# usb.net
KiCad netlist of a schematic drawn in Altium Designer
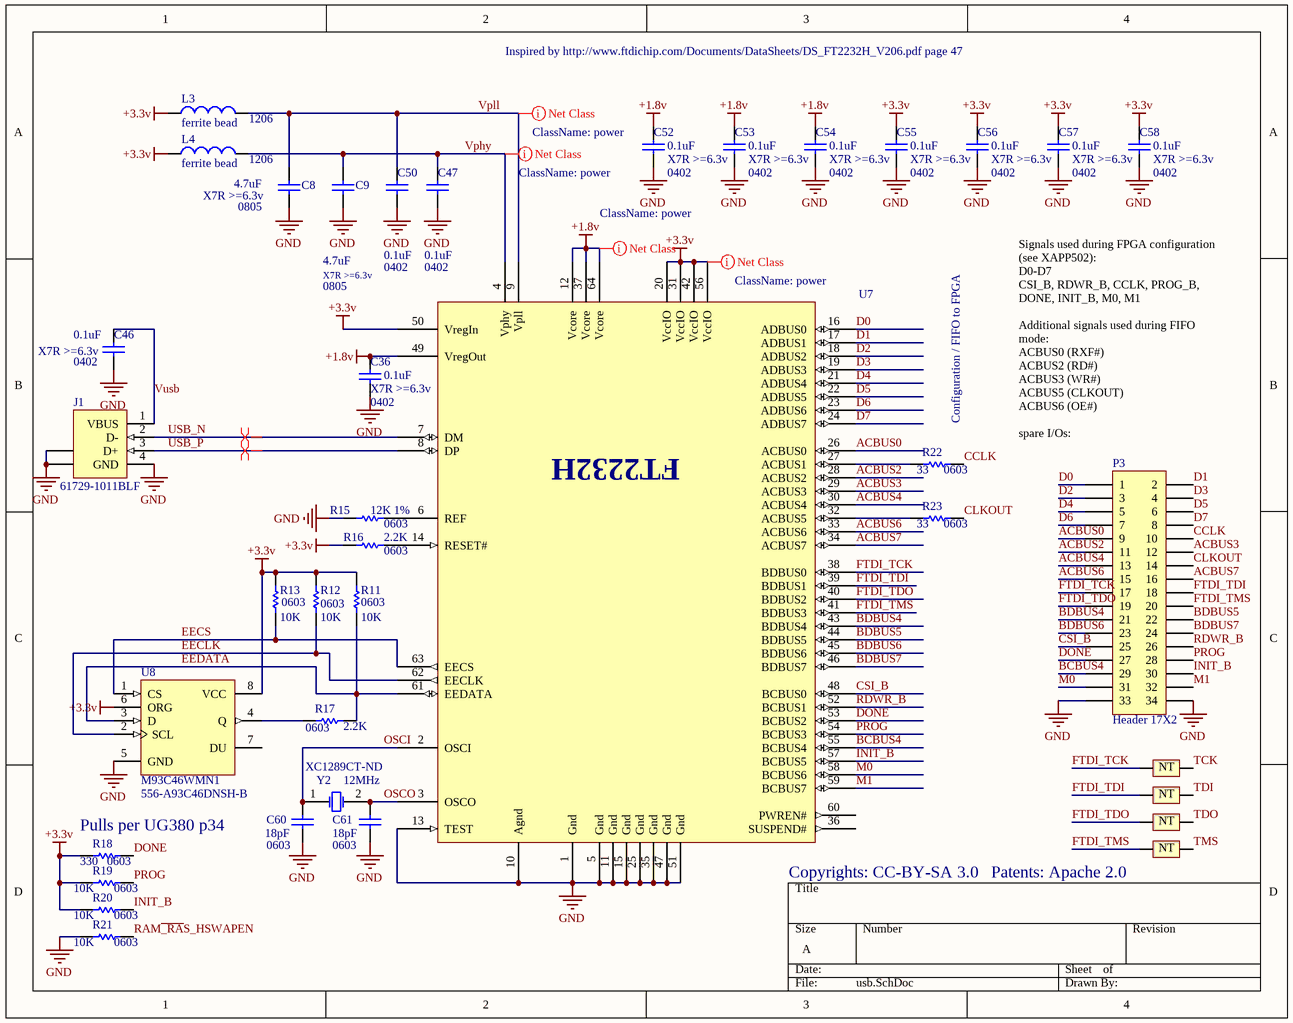
[diagram p0: usb.SchDoc]

(export (version "E")
  (design (tool "Eeschema 10.0.6"))
  (components
    (comp (ref "C8")
      (value "4.7uF")
      (footprint "CAPC2012N")
      (description "CAP CER 4.7UF 10V Y5V 0805")
      (fields
        (field (name "PACKAGEREFERENCE") "0805")
        (field (name "TOLERANCE") "-20%, +80%")
        (field (name "RATING") "X7R >=6.3v")
      )
      (libsource (lib "Miscellaneous Devices") (part "Cap"))
    )
    (comp (ref "C9")
      (value "4.7uF")
      (footprint "CAPC2012N")
      (description "CAP CER 4.7UF 10V Y5V 0805")
      (fields
        (field (name "PACKAGEREFERENCE") "0805")
        (field (name "TOLERANCE") "-20%, +80%")
        (field (name "RATING") "X7R >=6.3v")
      )
      (libsource (lib "Miscellaneous Devices") (part "Cap"))
    )
    (comp (ref "C36")
      (value "0.1uF")
      (footprint "CAPC1005N")
      (description "CAP CER 0.1UF 25V 10% X5R 0603")
      (fields
        (field (name "PACKAGEREFERENCE") "0402")
        (field (name "TOLERANCE") "±10%")
        (field (name "RATING") "X7R >=6.3v")
      )
      (libsource (lib "Miscellaneous Devices") (part "Cap Semi"))
    )
    (comp (ref "C46")
      (value "0.1uF")
      (footprint "CAPC1005N")
      (description "CAP CER 0.1UF 25V 10% X5R 0603")
      (fields
        (field (name "PACKAGEREFERENCE") "0402")
        (field (name "TOLERANCE") "±10%")
        (field (name "RATING") "X7R >=6.3v")
      )
      (libsource (lib "Miscellaneous Devices") (part "Cap Semi"))
    )
    (comp (ref "C47")
      (value "0.1uF")
      (footprint "CAPC1005N")
      (description "CAP CER 0.1UF 25V 10% X5R 0603")
      (fields (field (name "PACKAGEREFERENCE") "0402") (field (name "TOLERANCE") "±10%"))
      (libsource (lib "Miscellaneous Devices") (part "Cap Semi"))
    )
    (comp (ref "C50")
      (value "0.1uF")
      (footprint "CAPC1005N")
      (description "CAP CER 0.1UF 25V 10% X5R 0603")
      (fields (field (name "PACKAGEREFERENCE") "0402") (field (name "TOLERANCE") "±10%"))
      (libsource (lib "Miscellaneous Devices") (part "Cap Semi"))
    )
    (comp (ref "C52")
      (value "0.1uF")
      (footprint "CAPC1005N")
      (description "CAP CER 0.1UF 25V 10% X5R 0603")
      (fields
        (field (name "PACKAGEREFERENCE") "0402")
        (field (name "TOLERANCE") "±10%")
        (field (name "RATING") "X7R >=6.3v")
      )
      (libsource (lib "Miscellaneous Devices") (part "Cap Semi"))
    )
    (comp (ref "C53")
      (value "0.1uF")
      (footprint "CAPC1005N")
      (description "CAP CER 0.1UF 25V 10% X5R 0603")
      (fields
        (field (name "PACKAGEREFERENCE") "0402")
        (field (name "TOLERANCE") "±10%")
        (field (name "RATING") "X7R >=6.3v")
      )
      (libsource (lib "Miscellaneous Devices") (part "Cap Semi"))
    )
    (comp (ref "C54")
      (value "0.1uF")
      (footprint "CAPC1005N")
      (description "CAP CER 0.1UF 25V 10% X5R 0603")
      (fields
        (field (name "PACKAGEREFERENCE") "0402")
        (field (name "TOLERANCE") "±10%")
        (field (name "RATING") "X7R >=6.3v")
      )
      (libsource (lib "Miscellaneous Devices") (part "Cap Semi"))
    )
    (comp (ref "C55")
      (value "0.1uF")
      (footprint "CAPC1005N")
      (description "CAP CER 0.1UF 25V 10% X5R 0603")
      (fields
        (field (name "PACKAGEREFERENCE") "0402")
        (field (name "TOLERANCE") "±10%")
        (field (name "RATING") "X7R >=6.3v")
      )
      (libsource (lib "Miscellaneous Devices") (part "Cap Semi"))
    )
    (comp (ref "C56")
      (value "0.1uF")
      (footprint "CAPC1005N")
      (description "CAP CER 0.1UF 25V 10% X5R 0603")
      (fields
        (field (name "PACKAGEREFERENCE") "0402")
        (field (name "TOLERANCE") "±10%")
        (field (name "RATING") "X7R >=6.3v")
      )
      (libsource (lib "Miscellaneous Devices") (part "Cap Semi"))
    )
    (comp (ref "C57")
      (value "0.1uF")
      (footprint "CAPC1005N")
      (description "CAP CER 0.1UF 25V 10% X5R 0603")
      (fields
        (field (name "PACKAGEREFERENCE") "0402")
        (field (name "TOLERANCE") "±10%")
        (field (name "RATING") "X7R >=6.3v")
      )
      (libsource (lib "Miscellaneous Devices") (part "Cap Semi"))
    )
    (comp (ref "C58")
      (value "0.1uF")
      (footprint "CAPC1005N")
      (description "CAP CER 0.1UF 25V 10% X5R 0603")
      (fields
        (field (name "PACKAGEREFERENCE") "0402")
        (field (name "TOLERANCE") "±10%")
        (field (name "RATING") "X7R >=6.3v")
      )
      (libsource (lib "Miscellaneous Devices") (part "Cap Semi"))
    )
    (comp (ref "C60")
      (value "18pF")
      (footprint "Chip_Capacitor_N:CAPC1608N")
      (description "Capacitor (Semiconductor SIM Model)")
      (fields (field (name "PACKAGEREFERENCE") "0603") (field (name "Comment") "Cap Semi"))
      (libsource (lib "Miscellaneous Devices") (part "Cap Semi"))
    )
    (comp (ref "C61")
      (value "18pF")
      (footprint "Chip_Capacitor_N:CAPC1608N")
      (description "Capacitor (Semiconductor SIM Model)")
      (fields (field (name "PACKAGEREFERENCE") "0603") (field (name "Comment") "Cap Semi"))
      (libsource (lib "Miscellaneous Devices") (part "Cap Semi"))
    )
    (comp (ref "J1")
      (value "61729-1011BLF")
      (footprint "1-1470156")
      (description "USB 1.1, Right Angle, Thru-Hole, B Type, Receptacle, 4 Position, White")
      (fields (field (name "Comment") "1-1470156-1"))
      (libsource (lib "AMP Serial Bus USB") (part "1-1470156-1"))
    )
    (comp (ref "L3")
      (value "ferrite bead")
      (footprint "INDC3216AN")
      (description "Inductor")
      (fields (field (name "PACKAGEREFERENCE") "1206"))
      (libsource (lib "Miscellaneous Devices") (part "Inductor"))
    )
    (comp (ref "L4")
      (value "ferrite bead")
      (footprint "INDC3216AN")
      (description "Inductor")
      (fields (field (name "PACKAGEREFERENCE") "1206"))
      (libsource (lib "Miscellaneous Devices") (part "Inductor"))
    )
    (comp (ref "NT2")
      (value "Net Tie2")
      (footprint "NetTie 0603")
      (description "0603 Net Tie to connect 2 different nets")
      (libsource (lib "OpenVizsla symbols") (part "Net Tie2"))
    )
    (comp (ref "NT3")
      (value "Net Tie2")
      (footprint "NetTie 0603")
      (description "0603 Net Tie to connect 2 different nets")
      (libsource (lib "OpenVizsla symbols") (part "Net Tie2"))
    )
    (comp (ref "NT4")
      (value "Net Tie2")
      (footprint "NetTie 0603")
      (description "0603 Net Tie to connect 2 different nets")
      (libsource (lib "OpenVizsla symbols") (part "Net Tie2"))
    )
    (comp (ref "NT5")
      (value "Net Tie2")
      (footprint "NetTie 0603")
      (description "0603 Net Tie to connect 2 different nets")
      (libsource (lib "OpenVizsla symbols") (part "Net Tie2"))
    )
    (comp (ref "P3")
      (value "Header 17X2")
      (footprint "HDR2X17")
      (description "Header, 17-Pin, Dual row")
      (libsource (lib "Miscellaneous Connectors") (part "Header 17X2"))
    )
    (comp (ref "R11")
      (value "10K")
      (footprint "RESC1608N")
      (description "Semiconductor Resistor")
      (fields (field (name "PACKAGEREFERENCE") "0603") (field (name "Comment") "Res Semi"))
      (libsource (lib "Miscellaneous Devices") (part "Res Semi"))
    )
    (comp (ref "R12")
      (value "10K")
      (footprint "RESC1608N")
      (description "Semiconductor Resistor")
      (fields (field (name "PACKAGEREFERENCE") "0603") (field (name "Comment") "Res Semi"))
      (libsource (lib "Miscellaneous Devices") (part "Res Semi"))
    )
    (comp (ref "R13")
      (value "10K")
      (footprint "RESC1608N")
      (description "Semiconductor Resistor")
      (fields (field (name "PACKAGEREFERENCE") "0603") (field (name "Comment") "Res Semi"))
      (libsource (lib "Miscellaneous Devices") (part "Res Semi"))
    )
    (comp (ref "R15")
      (value "12K 1%")
      (footprint "RESC1608N")
      (description "Semiconductor Resistor")
      (fields (field (name "PACKAGEREFERENCE") "0603") (field (name "Comment") "Res Semi"))
      (libsource (lib "Miscellaneous Devices") (part "Res Semi"))
    )
    (comp (ref "R16")
      (value "2.2K")
      (footprint "RESC1608N")
      (description "Semiconductor Resistor")
      (fields (field (name "PACKAGEREFERENCE") "0603") (field (name "Comment") "Res Semi"))
      (libsource (lib "Miscellaneous Devices") (part "Res Semi"))
    )
    (comp (ref "R17")
      (value "2.2K")
      (footprint "RESC1608N")
      (description "Semiconductor Resistor")
      (fields (field (name "PACKAGEREFERENCE") "0603") (field (name "Comment") "Res Semi"))
      (libsource (lib "Miscellaneous Devices") (part "Res Semi"))
    )
    (comp (ref "R18")
      (value "330")
      (footprint "RESC1608N")
      (description "Semiconductor Resistor")
      (fields (field (name "PACKAGEREFERENCE") "0603") (field (name "Comment") "Res Semi"))
      (libsource (lib "Miscellaneous Devices") (part "Res Semi"))
    )
    (comp (ref "R19")
      (value "10K")
      (footprint "RESC1608N")
      (description "Semiconductor Resistor")
      (fields (field (name "PACKAGEREFERENCE") "0603") (field (name "Comment") "Res Semi"))
      (libsource (lib "Miscellaneous Devices") (part "Res Semi"))
    )
    (comp (ref "R20")
      (value "10K")
      (footprint "RESC1608N")
      (description "Semiconductor Resistor")
      (fields (field (name "PACKAGEREFERENCE") "0603") (field (name "Comment") "Res Semi"))
      (libsource (lib "Miscellaneous Devices") (part "Res Semi"))
    )
    (comp (ref "R21")
      (value "10K")
      (footprint "RESC1608N")
      (description "Semiconductor Resistor")
      (fields (field (name "PACKAGEREFERENCE") "0603") (field (name "Comment") "Res Semi"))
      (libsource (lib "Miscellaneous Devices") (part "Res Semi"))
    )
    (comp (ref "R22")
      (value "33")
      (footprint "RESC1608N")
      (description "Semiconductor Resistor")
      (fields (field (name "PACKAGEREFERENCE") "0603") (field (name "Comment") "Res Semi"))
      (libsource (lib "Miscellaneous Devices") (part "Res Semi"))
    )
    (comp (ref "R23")
      (value "33")
      (footprint "RESC1608N")
      (description "Semiconductor Resistor")
      (fields (field (name "PACKAGEREFERENCE") "0603") (field (name "Comment") "Res Semi"))
      (libsource (lib "Miscellaneous Devices") (part "Res Semi"))
    )
    (comp (ref "U7")
      (value "Component_1")
      (footprint "SQFP50P1200X1200X180-64N")
      (description "FT2232H")
      (libsource (lib "ftdi") (part "Component_1"))
    )
    (comp (ref "U8")
      (value "M93C46WMN1")
      (footprint "SOP8_N")
      (description "1Kb (x8/x16) Serial Microwire Bus EEPROM")
      (fields (field (name "SUPPLIER PART NUMBER 1") "556-A93C46DNSH-B"))
      (libsource (lib "ST Memory EEPROM Serial") (part "M93C46WMN1"))
    )
    (comp (ref "Y2")
      (value "12MHz")
      (footprint "HC49/4H_SMX")
      (description "Crystal Oscillator")
      (fields (field (name "SUPPLIER PART NUMBER 1") "XC1289CT-ND"))
      (libsource (lib "Miscellaneous Devices") (part "XTAL"))
    )
  )
  (nets
    (net (code "1") (name "+1.8v") (class "Default")
      (node (ref "C36") (pin "2") (pinfunction "2_2") (pintype "passive"))
      (node (ref "C52") (pin "2") (pinfunction "2_2") (pintype "passive"))
      (node (ref "C53") (pin "2") (pinfunction "2_2") (pintype "passive"))
      (node (ref "C54") (pin "2") (pinfunction "2_2") (pintype "passive"))
      (node (ref "U7") (pin "12") (pinfunction "Vcore_12") (pintype "power_in"))
      (node (ref "U7") (pin "37") (pinfunction "Vcore_37") (pintype "power_in"))
      (node (ref "U7") (pin "49") (pinfunction "VregOut_49") (pintype "power_in"))
      (node (ref "U7") (pin "64") (pinfunction "Vcore_64") (pintype "power_in"))
    )
    (net (code "2") (name "+3.3v") (class "Default")
      (node (ref "C55") (pin "2") (pinfunction "2_2") (pintype "passive"))
      (node (ref "C56") (pin "2") (pinfunction "2_2") (pintype "passive"))
      (node (ref "C57") (pin "2") (pinfunction "2_2") (pintype "passive"))
      (node (ref "C58") (pin "2") (pinfunction "2_2") (pintype "passive"))
      (node (ref "L3") (pin "1") (pinfunction "1_1") (pintype "passive"))
      (node (ref "L4") (pin "1") (pinfunction "1_1") (pintype "passive"))
      (node (ref "R11") (pin "2") (pinfunction "2_2") (pintype "passive"))
      (node (ref "R12") (pin "2") (pinfunction "2_2") (pintype "passive"))
      (node (ref "R13") (pin "2") (pinfunction "2_2") (pintype "passive"))
      (node (ref "R16") (pin "1") (pinfunction "1_1") (pintype "passive"))
      (node (ref "R18") (pin "2") (pinfunction "2_2") (pintype "passive"))
      (node (ref "R19") (pin "1") (pinfunction "1_1") (pintype "passive"))
      (node (ref "R20") (pin "1") (pinfunction "1_1") (pintype "passive"))
      (node (ref "U7") (pin "20") (pinfunction "VccIO_20") (pintype "power_in"))
      (node (ref "U7") (pin "31") (pinfunction "VccIO_31") (pintype "power_in"))
      (node (ref "U7") (pin "42") (pinfunction "VccIO_42") (pintype "power_in"))
      (node (ref "U7") (pin "50") (pinfunction "VregIn_50") (pintype "power_in"))
      (node (ref "U7") (pin "56") (pinfunction "VccIO_56") (pintype "power_in"))
      (node (ref "U8") (pin "6") (pinfunction "ORG_6") (pintype "passive"))
      (node (ref "U8") (pin "8") (pinfunction "VCC_8") (pintype "power_in"))
    )
    (net (code "3") (name "/ACBUS0") (class "Default")
      (node (ref "P3") (pin "9") (pinfunction "9_9") (pintype "passive"))
      (node (ref "U7") (pin "26") (pinfunction "ACBUS0_26") (pintype "bidirectional"))
    )
    (net (code "4") (name "/ACBUS2") (class "Default")
      (node (ref "P3") (pin "11") (pinfunction "11_11") (pintype "passive"))
      (node (ref "U7") (pin "28") (pinfunction "ACBUS2_28") (pintype "bidirectional"))
    )
    (net (code "5") (name "/ACBUS3") (class "Default")
      (node (ref "P3") (pin "12") (pinfunction "12_12") (pintype "passive"))
      (node (ref "U7") (pin "29") (pinfunction "ACBUS3_29") (pintype "bidirectional"))
    )
    (net (code "6") (name "/ACBUS4") (class "Default")
      (node (ref "P3") (pin "13") (pinfunction "13_13") (pintype "passive"))
      (node (ref "U7") (pin "30") (pinfunction "ACBUS4_30") (pintype "bidirectional"))
    )
    (net (code "7") (name "/ACBUS6") (class "Default")
      (node (ref "P3") (pin "15") (pinfunction "15_15") (pintype "passive"))
      (node (ref "U7") (pin "33") (pinfunction "ACBUS6_33") (pintype "bidirectional"))
    )
    (net (code "8") (name "/ACBUS7") (class "Default")
      (node (ref "P3") (pin "16") (pinfunction "16_16") (pintype "passive"))
      (node (ref "U7") (pin "34") (pinfunction "ACBUS7_34") (pintype "bidirectional"))
    )
    (net (code "9") (name "/BCBUS4") (class "Default")
      (node (ref "P3") (pin "29") (pinfunction "29_29") (pintype "passive"))
      (node (ref "U7") (pin "55") (pinfunction "BCBUS4_55") (pintype "bidirectional"))
    )
    (net (code "10") (name "/BDBUS4") (class "Default")
      (node (ref "P3") (pin "21") (pinfunction "21_21") (pintype "passive"))
      (node (ref "U7") (pin "43") (pinfunction "BDBUS4_43") (pintype "bidirectional"))
    )
    (net (code "11") (name "/BDBUS5") (class "Default")
      (node (ref "P3") (pin "22") (pinfunction "22_22") (pintype "passive"))
      (node (ref "U7") (pin "44") (pinfunction "BDBUS5_44") (pintype "bidirectional"))
    )
    (net (code "12") (name "/BDBUS6") (class "Default")
      (node (ref "P3") (pin "23") (pinfunction "23_23") (pintype "passive"))
      (node (ref "U7") (pin "45") (pinfunction "BDBUS6_45") (pintype "bidirectional"))
    )
    (net (code "13") (name "/BDBUS7") (class "Default")
      (node (ref "P3") (pin "24") (pinfunction "24_24") (pintype "passive"))
      (node (ref "U7") (pin "46") (pinfunction "BDBUS7_46") (pintype "bidirectional"))
    )
    (net (code "14") (name "/CCLK") (class "Default")
      (node (ref "P3") (pin "10") (pinfunction "10_10") (pintype "passive"))
      (node (ref "R22") (pin "2") (pinfunction "2_2") (pintype "passive"))
    )
    (net (code "15") (name "/CLKOUT") (class "Default")
      (node (ref "P3") (pin "14") (pinfunction "14_14") (pintype "passive"))
      (node (ref "R23") (pin "2") (pinfunction "2_2") (pintype "passive"))
    )
    (net (code "16") (name "/CSI_B") (class "Default")
      (node (ref "P3") (pin "25") (pinfunction "25_25") (pintype "passive"))
      (node (ref "U7") (pin "48") (pinfunction "BCBUS0_48") (pintype "bidirectional"))
    )
    (net (code "17") (name "/D0") (class "Default")
      (node (ref "P3") (pin "1") (pinfunction "1_1") (pintype "passive"))
      (node (ref "U7") (pin "16") (pinfunction "ADBUS0_16") (pintype "bidirectional"))
    )
    (net (code "18") (name "/D1") (class "Default")
      (node (ref "P3") (pin "2") (pinfunction "2_2") (pintype "passive"))
      (node (ref "U7") (pin "17") (pinfunction "ADBUS1_17") (pintype "bidirectional"))
    )
    (net (code "19") (name "/D2") (class "Default")
      (node (ref "P3") (pin "3") (pinfunction "3_3") (pintype "passive"))
      (node (ref "U7") (pin "18") (pinfunction "ADBUS2_18") (pintype "bidirectional"))
    )
    (net (code "20") (name "/D3") (class "Default")
      (node (ref "P3") (pin "4") (pinfunction "4_4") (pintype "passive"))
      (node (ref "U7") (pin "19") (pinfunction "ADBUS3_19") (pintype "bidirectional"))
    )
    (net (code "21") (name "/D4") (class "Default")
      (node (ref "P3") (pin "5") (pinfunction "5_5") (pintype "passive"))
      (node (ref "U7") (pin "21") (pinfunction "ADBUS4_21") (pintype "bidirectional"))
    )
    (net (code "22") (name "/D5") (class "Default")
      (node (ref "P3") (pin "6") (pinfunction "6_6") (pintype "passive"))
      (node (ref "U7") (pin "22") (pinfunction "ADBUS5_22") (pintype "bidirectional"))
    )
    (net (code "23") (name "/D6") (class "Default")
      (node (ref "P3") (pin "7") (pinfunction "7_7") (pintype "passive"))
      (node (ref "U7") (pin "23") (pinfunction "ADBUS6_23") (pintype "bidirectional"))
    )
    (net (code "24") (name "/D7") (class "Default")
      (node (ref "P3") (pin "8") (pinfunction "8_8") (pintype "passive"))
      (node (ref "U7") (pin "24") (pinfunction "ADBUS7_24") (pintype "bidirectional"))
    )
    (net (code "25") (name "/DONE") (class "Default")
      (node (ref "P3") (pin "27") (pinfunction "27_27") (pintype "passive"))
      (node (ref "R18") (pin "1") (pinfunction "1_1") (pintype "passive"))
      (node (ref "U7") (pin "53") (pinfunction "BCBUS2_53") (pintype "bidirectional"))
    )
    (net (code "26") (name "/EECLK") (class "Default")
      (node (ref "R12") (pin "1") (pinfunction "1_1") (pintype "passive"))
      (node (ref "U7") (pin "62") (pinfunction "EECLK_62") (pintype "output"))
      (node (ref "U8") (pin "2") (pinfunction "SCL_2") (pintype "input"))
    )
    (net (code "27") (name "/EECS") (class "Default")
      (node (ref "R13") (pin "1") (pinfunction "1_1") (pintype "passive"))
      (node (ref "U7") (pin "63") (pinfunction "EECS_63") (pintype "output"))
      (node (ref "U8") (pin "1") (pinfunction "CS_1") (pintype "input"))
    )
    (net (code "28") (name "/EEDATA") (class "Default")
      (node (ref "R11") (pin "1") (pinfunction "1_1") (pintype "passive"))
      (node (ref "R17") (pin "2") (pinfunction "2_2") (pintype "passive"))
      (node (ref "U7") (pin "61") (pinfunction "EEDATA_61") (pintype "bidirectional"))
      (node (ref "U8") (pin "3") (pinfunction "D_3") (pintype "input"))
    )
    (net (code "29") (name "/FTDI_TCK") (class "Default")
      (node (ref "NT2") (pin "1") (pinfunction "1_1") (pintype "passive"))
      (node (ref "P3") (pin "17") (pinfunction "17_17") (pintype "passive"))
      (node (ref "U7") (pin "38") (pinfunction "BDBUS0_38") (pintype "bidirectional"))
    )
    (net (code "30") (name "/FTDI_TDI") (class "Default")
      (node (ref "NT3") (pin "1") (pinfunction "1_1") (pintype "passive"))
      (node (ref "P3") (pin "18") (pinfunction "18_18") (pintype "passive"))
      (node (ref "U7") (pin "39") (pinfunction "BDBUS1_39") (pintype "bidirectional"))
    )
    (net (code "31") (name "/FTDI_TDO") (class "Default")
      (node (ref "NT4") (pin "1") (pinfunction "1_1") (pintype "passive"))
      (node (ref "P3") (pin "19") (pinfunction "19_19") (pintype "passive"))
      (node (ref "U7") (pin "40") (pinfunction "BDBUS2_40") (pintype "bidirectional"))
    )
    (net (code "32") (name "/FTDI_TMS") (class "Default")
      (node (ref "NT5") (pin "1") (pinfunction "1_1") (pintype "passive"))
      (node (ref "P3") (pin "20") (pinfunction "20_20") (pintype "passive"))
      (node (ref "U7") (pin "41") (pinfunction "BDBUS3_41") (pintype "bidirectional"))
    )
    (net (code "33") (name "/INIT_B") (class "Default")
      (node (ref "P3") (pin "30") (pinfunction "30_30") (pintype "passive"))
      (node (ref "R20") (pin "2") (pinfunction "2_2") (pintype "passive"))
      (node (ref "U7") (pin "57") (pinfunction "BCBUS5_57") (pintype "bidirectional"))
    )
    (net (code "34") (name "/M0") (class "Default")
      (node (ref "P3") (pin "31") (pinfunction "31_31") (pintype "passive"))
      (node (ref "U7") (pin "58") (pinfunction "BCBUS6_58") (pintype "bidirectional"))
    )
    (net (code "35") (name "/M1") (class "Default")
      (node (ref "P3") (pin "32") (pinfunction "32_32") (pintype "passive"))
      (node (ref "U7") (pin "59") (pinfunction "BCBUS7_59") (pintype "bidirectional"))
    )
    (net (code "36") (name "/OSCI") (class "Default")
      (node (ref "C60") (pin "2") (pinfunction "2_2") (pintype "passive"))
      (node (ref "U7") (pin "2") (pinfunction "OSCI_2") (pintype "passive"))
      (node (ref "Y2") (pin "1") (pinfunction "OSC1_1") (pintype "passive"))
    )
    (net (code "37") (name "/OSCO") (class "Default")
      (node (ref "C61") (pin "2") (pinfunction "2_2") (pintype "passive"))
      (node (ref "U7") (pin "3") (pinfunction "OSCO_3") (pintype "passive"))
      (node (ref "Y2") (pin "2") (pinfunction "OSC2_2") (pintype "passive"))
    )
    (net (code "38") (name "/PROG") (class "Default")
      (node (ref "P3") (pin "28") (pinfunction "28_28") (pintype "passive"))
      (node (ref "R19") (pin "2") (pinfunction "2_2") (pintype "passive"))
      (node (ref "U7") (pin "54") (pinfunction "BCBUS3_54") (pintype "bidirectional"))
    )
    (net (code "39") (name "/RAM~{_RA}S_HSWAPEN") (class "Default")
      (node (ref "R21") (pin "2") (pinfunction "2_2") (pintype "passive"))
    )
    (net (code "40") (name "/RDWR_B") (class "Default")
      (node (ref "P3") (pin "26") (pinfunction "26_26") (pintype "passive"))
      (node (ref "U7") (pin "52") (pinfunction "BCBUS1_52") (pintype "bidirectional"))
    )
    (net (code "41") (name "/TCK") (class "Default")
      (node (ref "NT2") (pin "2") (pinfunction "2_2") (pintype "passive"))
    )
    (net (code "42") (name "/TDI") (class "Default")
      (node (ref "NT3") (pin "2") (pinfunction "2_2") (pintype "passive"))
    )
    (net (code "43") (name "/TDO") (class "Default")
      (node (ref "NT4") (pin "2") (pinfunction "2_2") (pintype "passive"))
    )
    (net (code "44") (name "/TMS") (class "Default")
      (node (ref "NT5") (pin "2") (pinfunction "2_2") (pintype "passive"))
    )
    (net (code "45") (name "/USB_N") (class "Default")
      (node (ref "J1") (pin "2") (pinfunction "D-_2") (pintype "input"))
      (node (ref "U7") (pin "7") (pinfunction "DM_7") (pintype "bidirectional"))
    )
    (net (code "46") (name "/USB_P") (class "Default")
      (node (ref "J1") (pin "3") (pinfunction "D+_3") (pintype "input"))
      (node (ref "U7") (pin "8") (pinfunction "DP_8") (pintype "bidirectional"))
    )
    (net (code "47") (name "/Vphy") (class "Default")
      (node (ref "C47") (pin "2") (pinfunction "2_2") (pintype "passive"))
      (node (ref "C9") (pin "2") (pinfunction "2_2") (pintype "passive"))
      (node (ref "L4") (pin "2") (pinfunction "2_2") (pintype "passive"))
      (node (ref "U7") (pin "4") (pinfunction "Vphy_4") (pintype "power_in"))
    )
    (net (code "48") (name "/Vpll") (class "Default")
      (node (ref "C50") (pin "2") (pinfunction "2_2") (pintype "passive"))
      (node (ref "C8") (pin "2") (pinfunction "2_2") (pintype "passive"))
      (node (ref "L3") (pin "2") (pinfunction "2_2") (pintype "passive"))
      (node (ref "U7") (pin "9") (pinfunction "Vpll_9") (pintype "power_in"))
    )
    (net (code "49") (name "/Vusb") (class "Default")
      (node (ref "C46") (pin "2") (pinfunction "2_2") (pintype "passive"))
      (node (ref "J1") (pin "1") (pinfunction "VBUS_1") (pintype "power_in"))
    )
    (net (code "50") (name "GND") (class "Default")
      (node (ref "C36") (pin "1") (pinfunction "1_1") (pintype "passive"))
      (node (ref "C46") (pin "1") (pinfunction "1_1") (pintype "passive"))
      (node (ref "C47") (pin "1") (pinfunction "1_1") (pintype "passive"))
      (node (ref "C50") (pin "1") (pinfunction "1_1") (pintype "passive"))
      (node (ref "C52") (pin "1") (pinfunction "1_1") (pintype "passive"))
      (node (ref "C53") (pin "1") (pinfunction "1_1") (pintype "passive"))
      (node (ref "C54") (pin "1") (pinfunction "1_1") (pintype "passive"))
      (node (ref "C55") (pin "1") (pinfunction "1_1") (pintype "passive"))
      (node (ref "C56") (pin "1") (pinfunction "1_1") (pintype "passive"))
      (node (ref "C57") (pin "1") (pinfunction "1_1") (pintype "passive"))
      (node (ref "C58") (pin "1") (pinfunction "1_1") (pintype "passive"))
      (node (ref "C60") (pin "1") (pinfunction "1_1") (pintype "passive"))
      (node (ref "C61") (pin "1") (pinfunction "1_1") (pintype "passive"))
      (node (ref "C8") (pin "1") (pinfunction "1_1") (pintype "passive"))
      (node (ref "C9") (pin "1") (pinfunction "1_1") (pintype "passive"))
      (node (ref "J1") (pin "4") (pinfunction "GND_4") (pintype "power_in"))
      (node (ref "J1") (pin "5") (pinfunction "SHLD_5") (pintype "passive"))
      (node (ref "J1") (pin "6") (pinfunction "SHLD_6") (pintype "passive"))
      (node (ref "P3") (pin "33") (pinfunction "33_33") (pintype "passive"))
      (node (ref "P3") (pin "34") (pinfunction "34_34") (pintype "passive"))
      (node (ref "R15") (pin "2") (pinfunction "2_2") (pintype "passive"))
      (node (ref "R21") (pin "1") (pinfunction "1_1") (pintype "passive"))
      (node (ref "U7") (pin "1") (pinfunction "Gnd_1") (pintype "power_in"))
      (node (ref "U7") (pin "10") (pinfunction "Agnd_10") (pintype "power_in"))
      (node (ref "U7") (pin "11") (pinfunction "Gnd_11") (pintype "power_in"))
      (node (ref "U7") (pin "13") (pinfunction "TEST_13") (pintype "input"))
      (node (ref "U7") (pin "15") (pinfunction "Gnd_15") (pintype "power_in"))
      (node (ref "U7") (pin "25") (pinfunction "Gnd_25") (pintype "power_in"))
      (node (ref "U7") (pin "35") (pinfunction "Gnd_35") (pintype "power_in"))
      (node (ref "U7") (pin "47") (pinfunction "Gnd_47") (pintype "power_in"))
      (node (ref "U7") (pin "5") (pinfunction "Gnd_5") (pintype "power_in"))
      (node (ref "U7") (pin "51") (pinfunction "Gnd_51") (pintype "power_in"))
      (node (ref "U8") (pin "5") (pinfunction "GND_5") (pintype "power_in"))
    )
    (net (code "51") (name "Net-(U7-ACBUS1)") (class "Default")
      (node (ref "R22") (pin "1") (pinfunction "1_1") (pintype "passive"))
      (node (ref "U7") (pin "27") (pinfunction "ACBUS1_27") (pintype "bidirectional"))
    )
    (net (code "52") (name "Net-(U7-ACBUS5)") (class "Default")
      (node (ref "R23") (pin "1") (pinfunction "1_1") (pintype "passive"))
      (node (ref "U7") (pin "32") (pinfunction "ACBUS5_32") (pintype "bidirectional"))
    )
    (net (code "53") (name "Net-(U7-REF)") (class "Default")
      (node (ref "R15") (pin "1") (pinfunction "1_1") (pintype "passive"))
      (node (ref "U7") (pin "6") (pinfunction "REF_6") (pintype "passive"))
    )
    (net (code "54") (name "Net-(U7-RESET#)") (class "Default")
      (node (ref "R16") (pin "2") (pinfunction "2_2") (pintype "passive"))
      (node (ref "U7") (pin "14") (pinfunction "RESET#_14") (pintype "input"))
    )
    (net (code "55") (name "Net-(U8-Q)") (class "Default")
      (node (ref "R17") (pin "1") (pinfunction "1_1") (pintype "passive"))
      (node (ref "U8") (pin "4") (pinfunction "Q_4") (pintype "output"))
    )
    (net (code "56") (name "unconnected-(U7-PWREN#-Pad60)") (class "Default")
      (node (ref "U7") (pin "60") (pinfunction "PWREN#_60") (pintype "output"))
    )
    (net (code "57") (name "unconnected-(U7-SUSPEND#-Pad36)") (class "Default")
      (node (ref "U7") (pin "36") (pinfunction "SUSPEND#_36") (pintype "output"))
    )
    (net (code "58") (name "unconnected-(U8-DU-Pad7)") (class "Default")
      (node (ref "U8") (pin "7") (pinfunction "DU_7") (pintype "passive"))
    )
  )
)
